# Schematic_control_panou.net
KiCad netlist of a schematic drawn in EAGLE
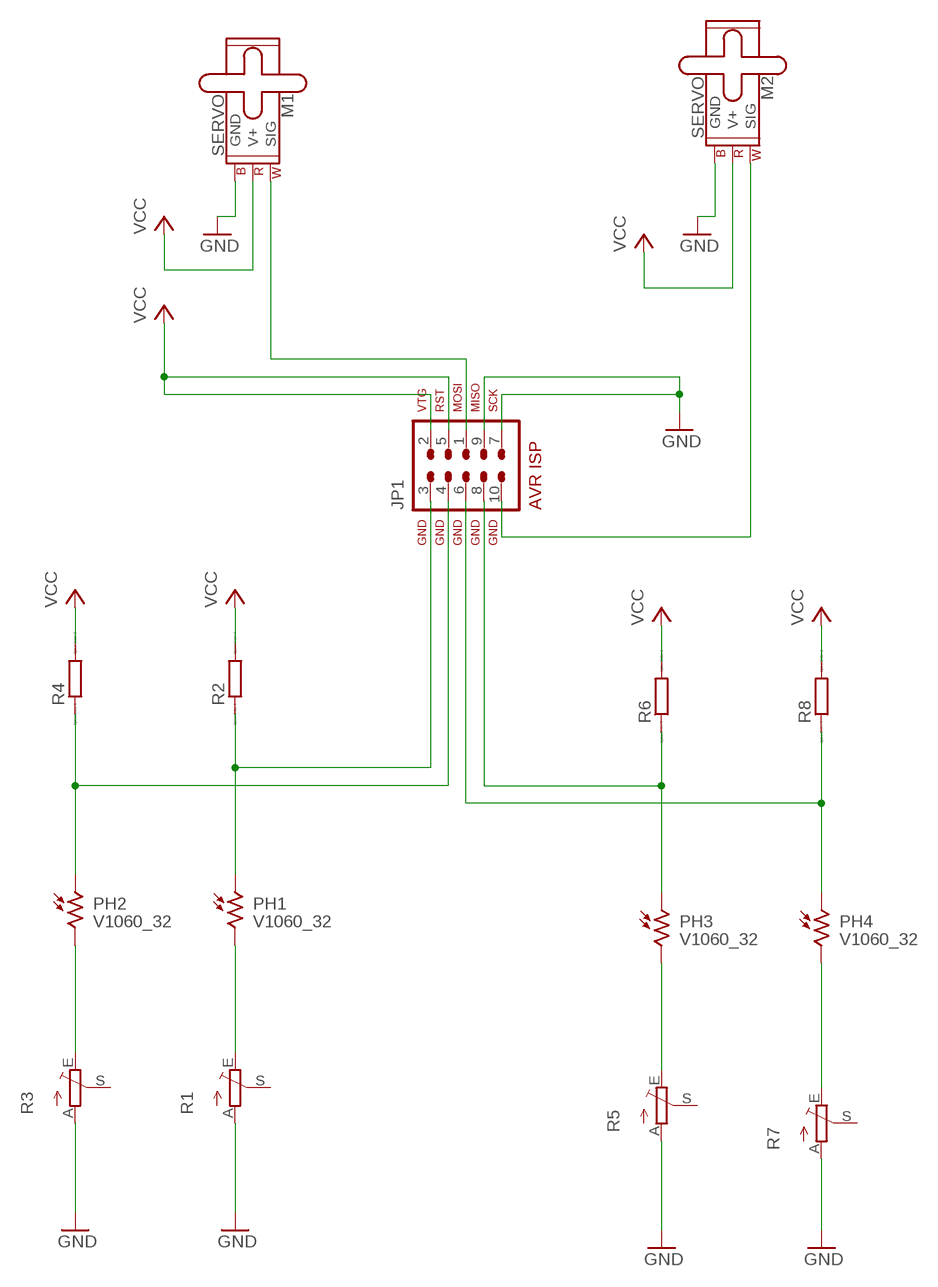
[diagram p0: schematic, sheet 1]

(export (version "E")
  (design (tool "Eeschema 10.0.6"))
  (components
    (comp (ref "JP1")
      (value "AVR-ISP-10")
      (footprint "eagle-import:AVR-ISP-10")
      (libsource (lib "eagle-import") (part "AVR-ISP-10"))
    )
    (comp (ref "M1")
      (value "SERVO")
      (footprint "eagle-import:1X03")
      (libsource (lib "eagle-import") (part "SERVO"))
    )
    (comp (ref "M2")
      (value "SERVO")
      (footprint "eagle-import:1X03")
      (libsource (lib "eagle-import") (part "SERVO"))
    )
    (comp (ref "PH1")
      (value "V1060_32")
      (footprint "eagle-import:TO-5_V10")
      (libsource (lib "eagle-import") (part "?1060V_32"))
    )
    (comp (ref "PH2")
      (value "V1060_32")
      (footprint "eagle-import:TO-5_V10")
      (libsource (lib "eagle-import") (part "?1060V_32"))
    )
    (comp (ref "PH3")
      (value "V1060_32")
      (footprint "eagle-import:TO-5_V10")
      (libsource (lib "eagle-import") (part "?1060V_32"))
    )
    (comp (ref "PH4")
      (value "V1060_32")
      (footprint "eagle-import:TO-5_V10")
      (libsource (lib "eagle-import") (part "?1060V_32"))
    )
    (comp (ref "R1")
      (value "TRIM_EU-S64W")
      (footprint "eagle-import:S64W")
      (libsource (lib "eagle-import") (part "TRIM_EU-S64W"))
    )
    (comp (ref "R2")
      (value "R0207/10")
      (footprint "eagle-import:0207_10")
      (libsource (lib "eagle-import") (part "R0207/10"))
    )
    (comp (ref "R3")
      (value "TRIM_EU-S64W")
      (footprint "eagle-import:S64W")
      (libsource (lib "eagle-import") (part "TRIM_EU-S64W"))
    )
    (comp (ref "R4")
      (value "R0207/10")
      (footprint "eagle-import:0207_10")
      (libsource (lib "eagle-import") (part "R0207/10"))
    )
    (comp (ref "R5")
      (value "TRIM_EU-S64W")
      (footprint "eagle-import:S64W")
      (libsource (lib "eagle-import") (part "TRIM_EU-S64W"))
    )
    (comp (ref "R6")
      (value "R0207/10")
      (footprint "eagle-import:0207_10")
      (libsource (lib "eagle-import") (part "R0207/10"))
    )
    (comp (ref "R7")
      (value "TRIM_EU-S64W")
      (footprint "eagle-import:S64W")
      (libsource (lib "eagle-import") (part "TRIM_EU-S64W"))
    )
    (comp (ref "R8")
      (value "R0207/10")
      (footprint "eagle-import:0207_10")
      (libsource (lib "eagle-import") (part "R0207/10"))
    )
  )
  (nets
    (net (code "1") (name "GND") (class "Default")
      (node (ref "JP1") (pin "7") (pinfunction "7_7") (pintype "passive"))
      (node (ref "JP1") (pin "9") (pinfunction "9_9") (pintype "passive"))
      (node (ref "M1") (pin "3") (pinfunction "GND_3") (pintype "bidirectional"))
      (node (ref "M2") (pin "3") (pinfunction "GND_3") (pintype "bidirectional"))
      (node (ref "R1") (pin "A") (pinfunction "A_A") (pintype "passive"))
      (node (ref "R3") (pin "A") (pinfunction "A_A") (pintype "passive"))
      (node (ref "R5") (pin "A") (pinfunction "A_A") (pintype "passive"))
      (node (ref "R7") (pin "A") (pinfunction "A_A") (pintype "passive"))
    )
    (net (code "2") (name "Net-(JP1-Pad3)") (class "Default")
      (node (ref "JP1") (pin "3") (pinfunction "3_3") (pintype "passive"))
      (node (ref "PH1") (pin "1") (pinfunction "1_1") (pintype "passive"))
      (node (ref "R2") (pin "1") (pinfunction "1_1") (pintype "passive"))
    )
    (net (code "3") (name "Net-(JP1-Pad4)") (class "Default")
      (node (ref "JP1") (pin "4") (pinfunction "4_4") (pintype "passive"))
      (node (ref "PH2") (pin "1") (pinfunction "1_1") (pintype "passive"))
      (node (ref "R4") (pin "1") (pinfunction "1_1") (pintype "passive"))
    )
    (net (code "4") (name "Net-(JP1-Pad6)") (class "Default")
      (node (ref "JP1") (pin "6") (pinfunction "6_6") (pintype "passive"))
      (node (ref "PH4") (pin "1") (pinfunction "1_1") (pintype "passive"))
      (node (ref "R8") (pin "1") (pinfunction "1_1") (pintype "passive"))
    )
    (net (code "5") (name "Net-(JP1-Pad8)") (class "Default")
      (node (ref "JP1") (pin "8") (pinfunction "8_8") (pintype "passive"))
      (node (ref "PH3") (pin "1") (pinfunction "1_1") (pintype "passive"))
      (node (ref "R6") (pin "1") (pinfunction "1_1") (pintype "passive"))
    )
    (net (code "6") (name "Net-(M1-SIG)") (class "Default")
      (node (ref "JP1") (pin "1") (pinfunction "1_1") (pintype "passive"))
      (node (ref "M1") (pin "1") (pinfunction "SIG_1") (pintype "bidirectional"))
    )
    (net (code "7") (name "Net-(M2-SIG)") (class "Default")
      (node (ref "JP1") (pin "10") (pinfunction "10_10") (pintype "passive"))
      (node (ref "M2") (pin "1") (pinfunction "SIG_1") (pintype "bidirectional"))
    )
    (net (code "8") (name "Net-(PH1-Pad2)") (class "Default")
      (node (ref "PH1") (pin "2") (pinfunction "2_2") (pintype "passive"))
      (node (ref "R1") (pin "E") (pinfunction "E_E") (pintype "passive"))
    )
    (net (code "9") (name "Net-(PH2-Pad2)") (class "Default")
      (node (ref "PH2") (pin "2") (pinfunction "2_2") (pintype "passive"))
      (node (ref "R3") (pin "E") (pinfunction "E_E") (pintype "passive"))
    )
    (net (code "10") (name "Net-(PH3-Pad2)") (class "Default")
      (node (ref "PH3") (pin "2") (pinfunction "2_2") (pintype "passive"))
      (node (ref "R5") (pin "E") (pinfunction "E_E") (pintype "passive"))
    )
    (net (code "11") (name "Net-(PH4-Pad2)") (class "Default")
      (node (ref "PH4") (pin "2") (pinfunction "2_2") (pintype "passive"))
      (node (ref "R7") (pin "E") (pinfunction "E_E") (pintype "passive"))
    )
    (net (code "12") (name "VCC") (class "Default")
      (node (ref "JP1") (pin "2") (pinfunction "2_2") (pintype "passive"))
      (node (ref "JP1") (pin "5") (pinfunction "5_5") (pintype "passive"))
      (node (ref "M1") (pin "2") (pinfunction "V+_2") (pintype "bidirectional"))
      (node (ref "M2") (pin "2") (pinfunction "V+_2") (pintype "bidirectional"))
      (node (ref "R2") (pin "2") (pinfunction "2_2") (pintype "passive"))
      (node (ref "R4") (pin "2") (pinfunction "2_2") (pintype "passive"))
      (node (ref "R6") (pin "2") (pinfunction "2_2") (pintype "passive"))
      (node (ref "R8") (pin "2") (pinfunction "2_2") (pintype "passive"))
    )
    (net (code "13") (name "unconnected-(R1-PadS)") (class "Default")
      (node (ref "R1") (pin "S") (pinfunction "S_S") (pintype "passive"))
    )
    (net (code "14") (name "unconnected-(R3-PadS)") (class "Default")
      (node (ref "R3") (pin "S") (pinfunction "S_S") (pintype "passive"))
    )
    (net (code "15") (name "unconnected-(R5-PadS)") (class "Default")
      (node (ref "R5") (pin "S") (pinfunction "S_S") (pintype "passive"))
    )
    (net (code "16") (name "unconnected-(R7-PadS)") (class "Default")
      (node (ref "R7") (pin "S") (pinfunction "S_S") (pintype "passive"))
    )
  )
)
